# untitled.net
KiCad netlist of a schematic drawn in EAGLE
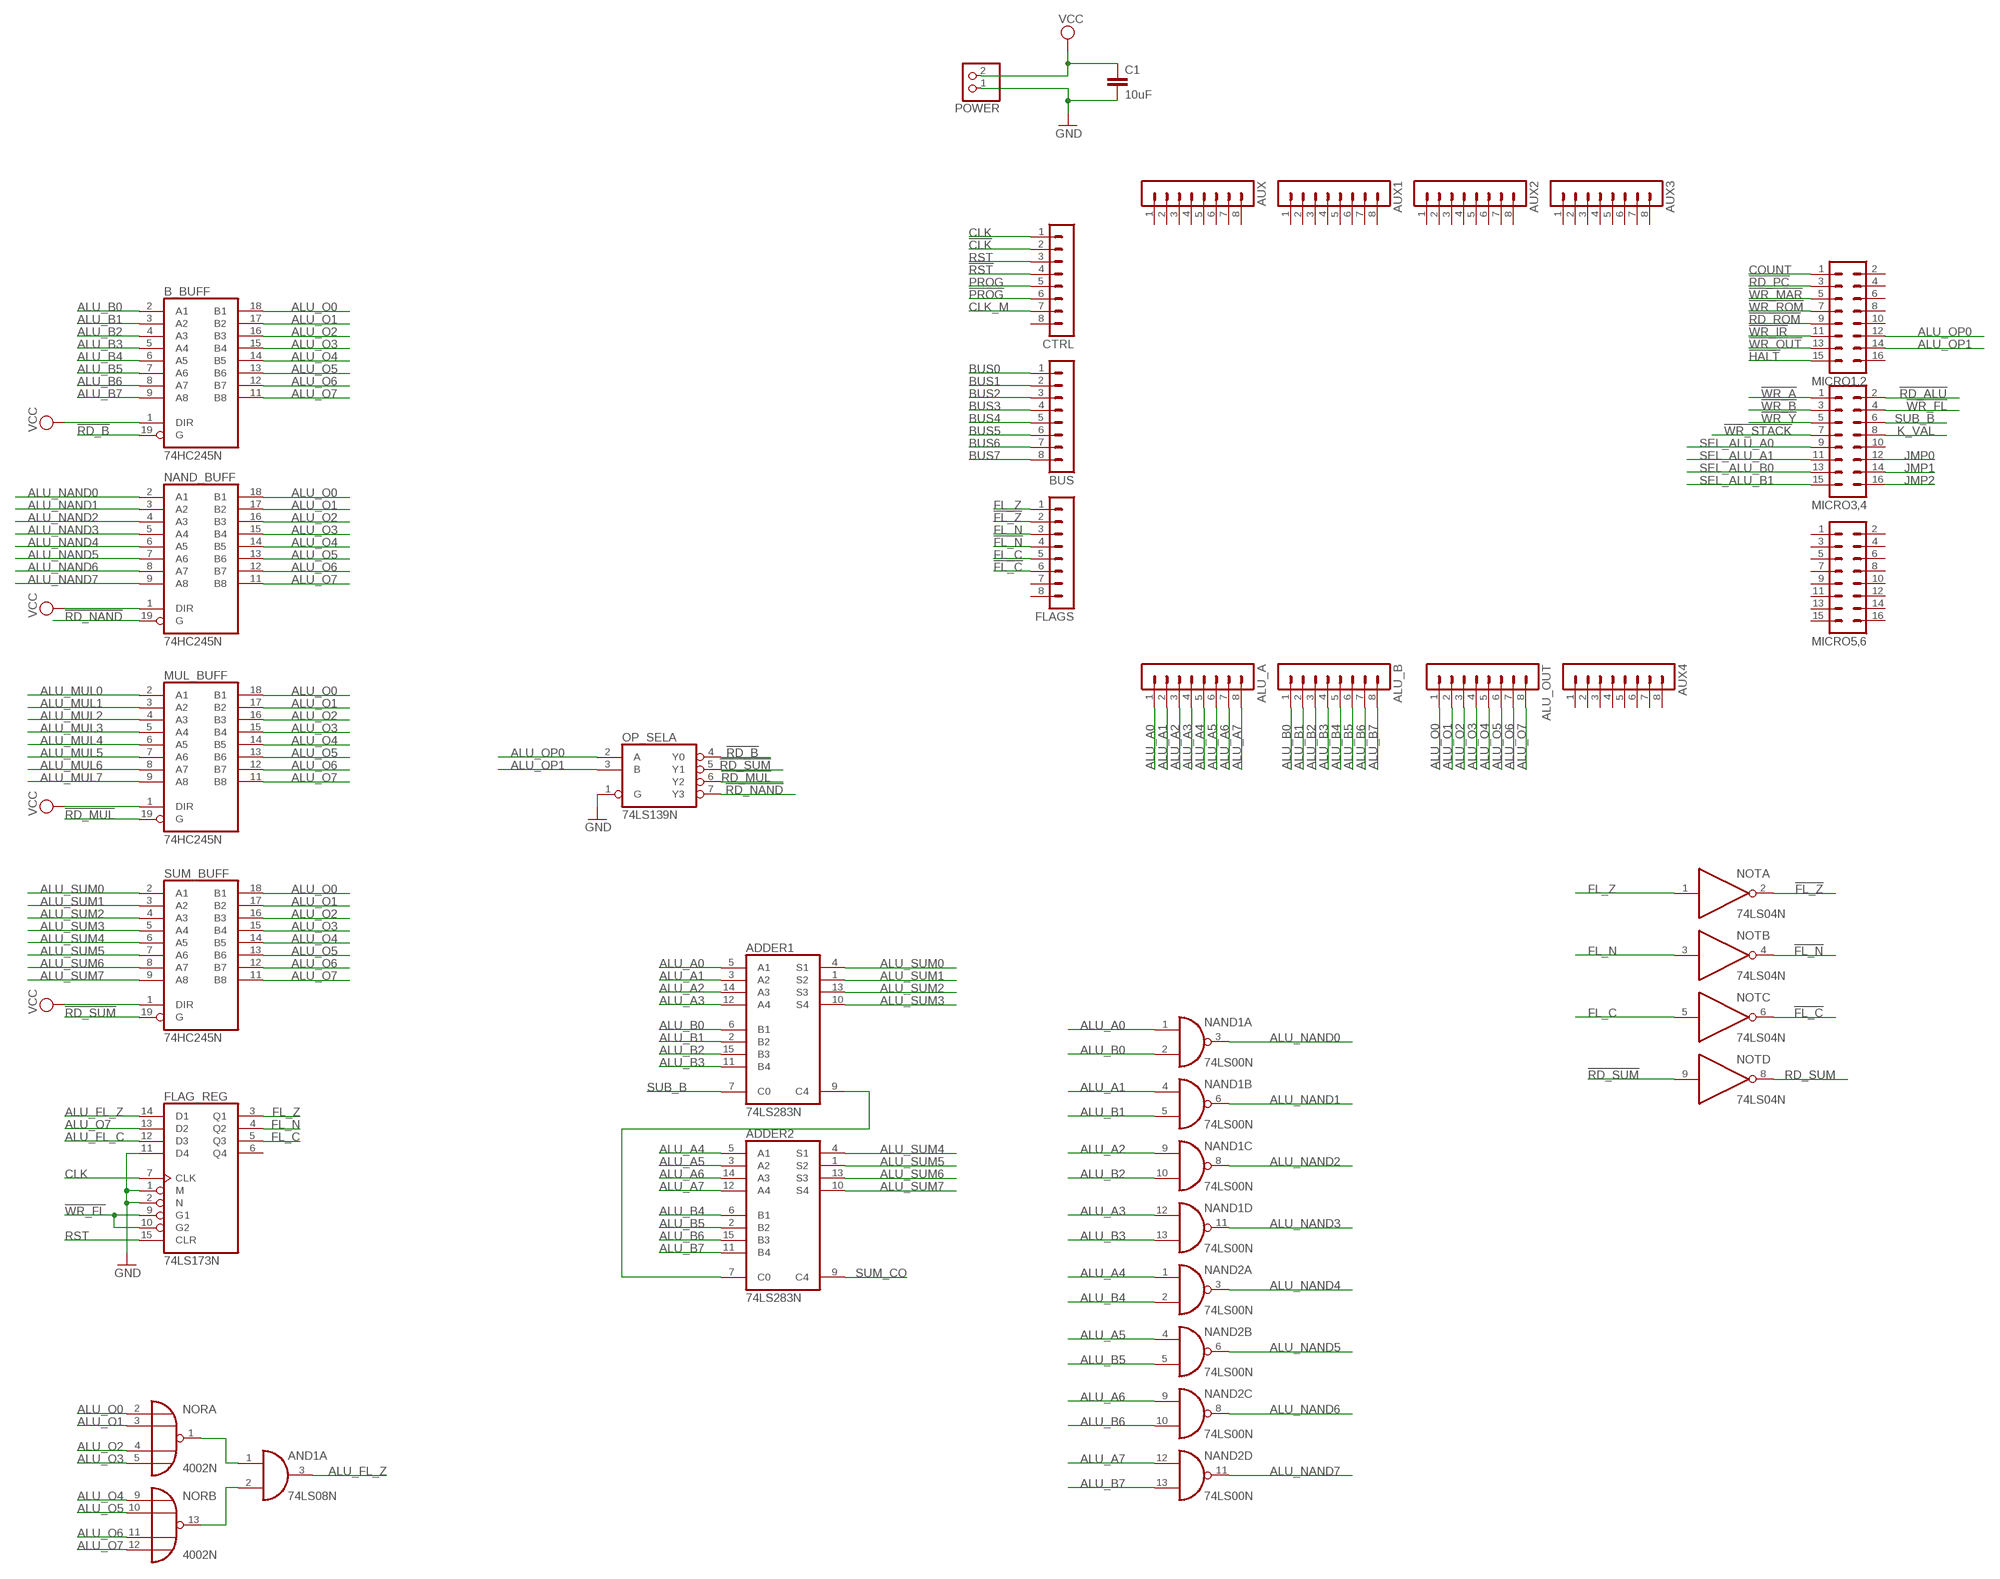
[diagram p0: schematic, sheet 1, part 1 of 2]
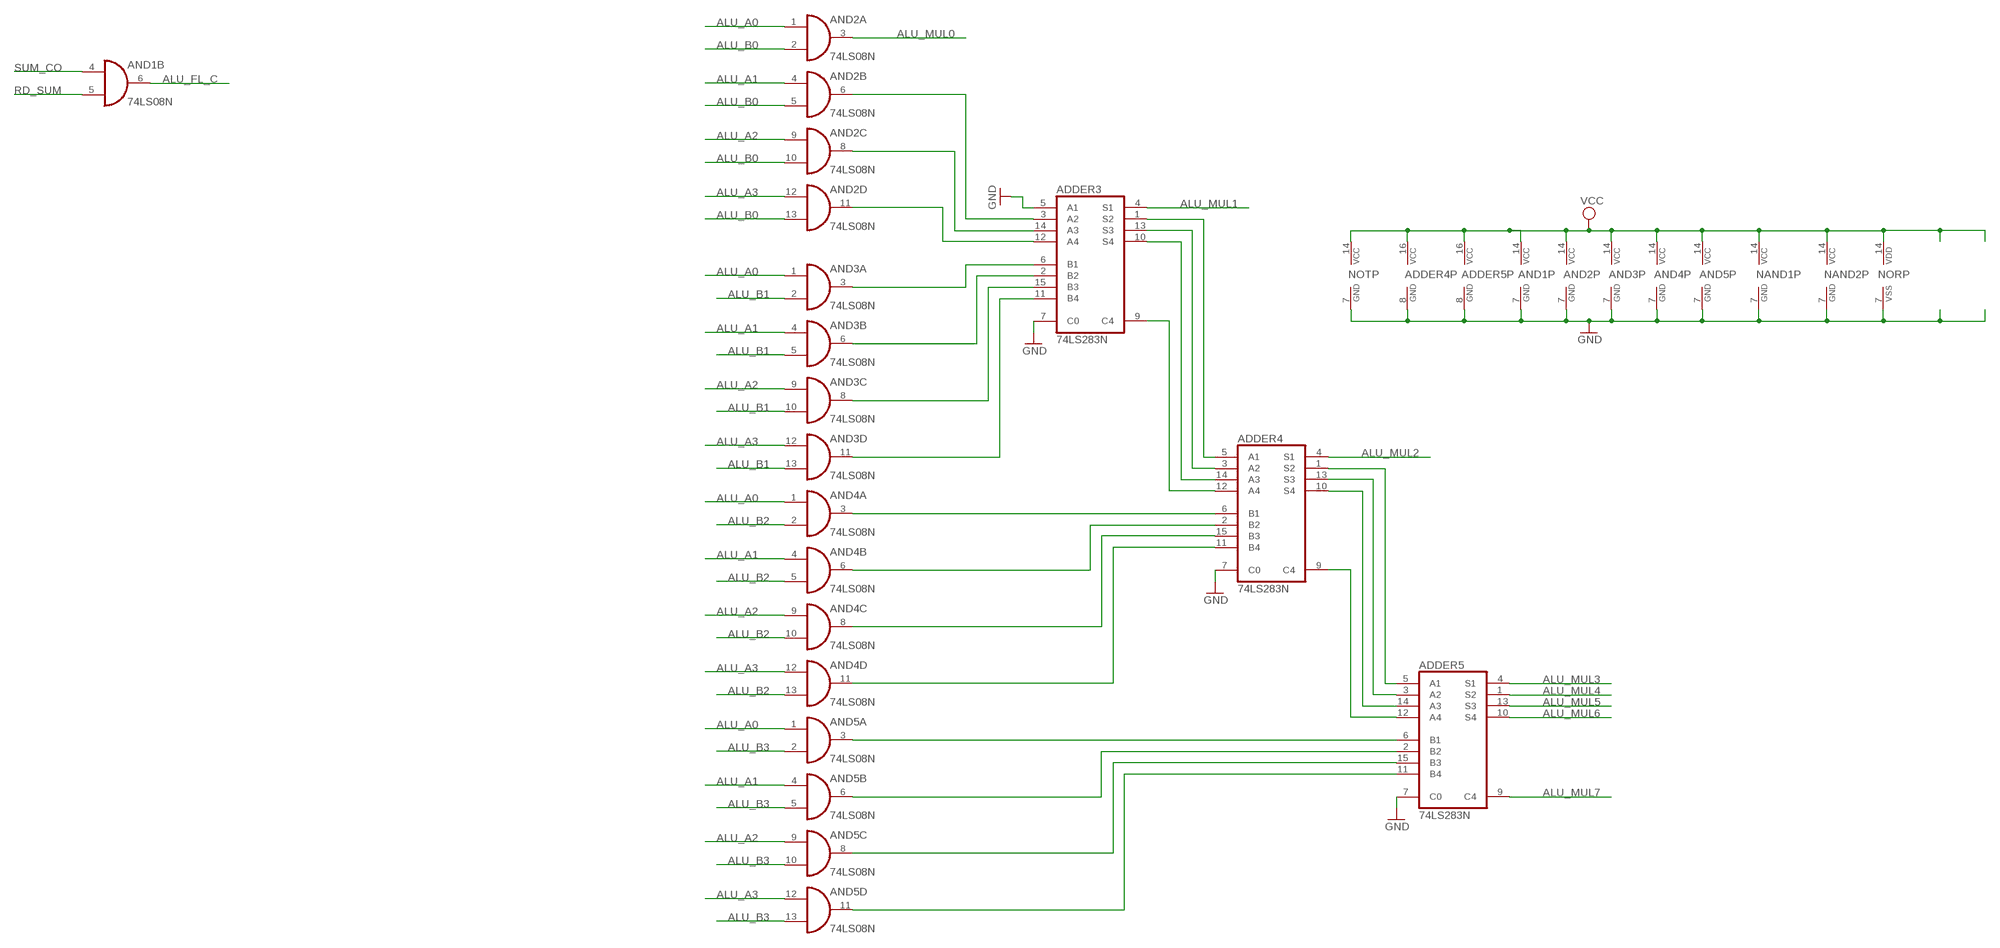
[diagram p1: schematic, sheet 1, part 2 of 2]

(export (version "E")
  (design (tool "Eeschema 10.0.6"))
  (components
    (comp (ref "ADDER1")
      (value "74LS283N")
      (footprint "eagle-import:DIL16")
      (libsource (lib "eagle-import") (part "74283NLS"))
    )
    (comp (ref "ADDER2")
      (value "74LS283N")
      (footprint "eagle-import:DIL16")
      (libsource (lib "eagle-import") (part "74283NLS"))
    )
    (comp (ref "ADDER3")
      (value "74LS283N")
      (footprint "eagle-import:DIL16")
      (libsource (lib "eagle-import") (part "74283NLS"))
    )
    (comp (ref "ADDER4")
      (value "74LS283N")
      (footprint "eagle-import:DIL16")
      (libsource (lib "eagle-import") (part "74283NLS"))
    )
    (comp (ref "ADDER5")
      (value "74LS283N")
      (footprint "eagle-import:DIL16")
      (libsource (lib "eagle-import") (part "74283NLS"))
    )
    (comp (ref "ALU_A")
      (value "MA08-1")
      (footprint "eagle-import:MA08-1")
      (libsource (lib "eagle-import") (part "MA08-1"))
    )
    (comp (ref "ALU_B")
      (value "MA08-1")
      (footprint "eagle-import:MA08-1")
      (libsource (lib "eagle-import") (part "MA08-1"))
    )
    (comp (ref "ALU_OUT")
      (value "MA08-1")
      (footprint "eagle-import:MA08-1")
      (libsource (lib "eagle-import") (part "MA08-1"))
    )
    (comp (ref "AND1")
      (value "74LS08N")
      (footprint "eagle-import:DIL14")
      (libsource (lib "eagle-import") (part "7408NLS"))
    )
    (comp (ref "AND2")
      (value "74LS08N")
      (footprint "eagle-import:DIL14")
      (libsource (lib "eagle-import") (part "7408NLS"))
    )
    (comp (ref "AND3")
      (value "74LS08N")
      (footprint "eagle-import:DIL14")
      (libsource (lib "eagle-import") (part "7408NLS"))
    )
    (comp (ref "AND4")
      (value "74LS08N")
      (footprint "eagle-import:DIL14")
      (libsource (lib "eagle-import") (part "7408NLS"))
    )
    (comp (ref "AND5")
      (value "74LS08N")
      (footprint "eagle-import:DIL14")
      (libsource (lib "eagle-import") (part "7408NLS"))
    )
    (comp (ref "AUX")
      (value "MA08-1")
      (footprint "eagle-import:MA08-1")
      (libsource (lib "eagle-import") (part "MA08-1"))
    )
    (comp (ref "AUX1")
      (value "MA08-1")
      (footprint "eagle-import:MA08-1")
      (libsource (lib "eagle-import") (part "MA08-1"))
    )
    (comp (ref "AUX2")
      (value "MA08-1")
      (footprint "eagle-import:MA08-1")
      (libsource (lib "eagle-import") (part "MA08-1"))
    )
    (comp (ref "AUX3")
      (value "MA08-1")
      (footprint "eagle-import:MA08-1")
      (libsource (lib "eagle-import") (part "MA08-1"))
    )
    (comp (ref "AUX4")
      (value "MA08-1")
      (footprint "eagle-import:MA08-1")
      (libsource (lib "eagle-import") (part "MA08-1"))
    )
    (comp (ref "BUS")
      (value "MA08-1")
      (footprint "eagle-import:MA08-1")
      (libsource (lib "eagle-import") (part "MA08-1"))
    )
    (comp (ref "B_BUFF")
      (value "74HC245N")
      (footprint "eagle-import:DIL20")
      (libsource (lib "eagle-import") (part "74245NHC"))
    )
    (comp (ref "C1")
      (value "10uF")
      (footprint "eagle-import:C025-050X050")
      (libsource (lib "eagle-import") (part "C-EU025-050X050"))
    )
    (comp (ref "CTRL")
      (value "MA08-1")
      (footprint "eagle-import:MA08-1")
      (libsource (lib "eagle-import") (part "MA08-1"))
    )
    (comp (ref "FLAGS")
      (value "MA08-1")
      (footprint "eagle-import:MA08-1")
      (libsource (lib "eagle-import") (part "MA08-1"))
    )
    (comp (ref "FLAG_REG")
      (value "74LS173N")
      (footprint "eagle-import:DIL16")
      (libsource (lib "eagle-import") (part "74173NLS"))
    )
    (comp (ref "MICRO1,2")
      (value "MA08-2")
      (footprint "eagle-import:MA08-2")
      (libsource (lib "eagle-import") (part "MA08-2"))
    )
    (comp (ref "MICRO3,4")
      (value "MA08-2")
      (footprint "eagle-import:MA08-2")
      (libsource (lib "eagle-import") (part "MA08-2"))
    )
    (comp (ref "MICRO5,6")
      (value "MA08-2")
      (footprint "eagle-import:MA08-2")
      (libsource (lib "eagle-import") (part "MA08-2"))
    )
    (comp (ref "MUL_BUFF")
      (value "74HC245N")
      (footprint "eagle-import:DIL20")
      (libsource (lib "eagle-import") (part "74245NHC"))
    )
    (comp (ref "NAND1")
      (value "74LS00N")
      (footprint "eagle-import:DIL14")
      (libsource (lib "eagle-import") (part "7400NLS"))
    )
    (comp (ref "NAND2")
      (value "74LS00N")
      (footprint "eagle-import:DIL14")
      (libsource (lib "eagle-import") (part "7400NLS"))
    )
    (comp (ref "NAND_BUFF")
      (value "74HC245N")
      (footprint "eagle-import:DIL20")
      (libsource (lib "eagle-import") (part "74245NHC"))
    )
    (comp (ref "NOR")
      (value "4002N")
      (footprint "eagle-import:DIL14")
      (libsource (lib "eagle-import") (part "4002N"))
    )
    (comp (ref "NOT")
      (value "74LS04N")
      (footprint "eagle-import:DIL14")
      (libsource (lib "eagle-import") (part "7404NLS"))
    )
    (comp (ref "OP_SEL")
      (value "74LS139N")
      (footprint "eagle-import:DIL16")
      (libsource (lib "eagle-import") (part "74139NLS"))
    )
    (comp (ref "POWER")
      (value "PINHD-1X2")
      (footprint "eagle-import:1X02")
      (libsource (lib "eagle-import") (part "PINHD-1X2"))
    )
    (comp (ref "SUM_BUFF")
      (value "74HC245N")
      (footprint "eagle-import:DIL20")
      (libsource (lib "eagle-import") (part "74245NHC"))
    )
  )
  (nets
    (net (code "1") (name "ALU_A0") (class "Default")
      (node (ref "ADDER1") (pin "5") (pinfunction "A1_5") (pintype "input"))
      (node (ref "ALU_A") (pin "1") (pinfunction "1_1") (pintype "passive"))
      (node (ref "AND2") (pin "1") (pinfunction "I0_1") (pintype "input"))
      (node (ref "AND3") (pin "1") (pinfunction "I0_1") (pintype "input"))
      (node (ref "AND4") (pin "1") (pinfunction "I0_1") (pintype "input"))
      (node (ref "AND5") (pin "1") (pinfunction "I0_1") (pintype "input"))
      (node (ref "NAND1") (pin "1") (pinfunction "I0_1") (pintype "input"))
    )
    (net (code "2") (name "ALU_A1") (class "Default")
      (node (ref "ADDER1") (pin "3") (pinfunction "A2_3") (pintype "input"))
      (node (ref "ALU_A") (pin "2") (pinfunction "2_2") (pintype "passive"))
      (node (ref "AND2") (pin "4") (pinfunction "I0_4") (pintype "input"))
      (node (ref "AND3") (pin "4") (pinfunction "I0_4") (pintype "input"))
      (node (ref "AND4") (pin "4") (pinfunction "I0_4") (pintype "input"))
      (node (ref "AND5") (pin "4") (pinfunction "I0_4") (pintype "input"))
      (node (ref "NAND1") (pin "4") (pinfunction "I0_4") (pintype "input"))
    )
    (net (code "3") (name "ALU_A2") (class "Default")
      (node (ref "ADDER1") (pin "14") (pinfunction "A3_14") (pintype "input"))
      (node (ref "ALU_A") (pin "3") (pinfunction "3_3") (pintype "passive"))
      (node (ref "AND2") (pin "9") (pinfunction "I0_9") (pintype "input"))
      (node (ref "AND3") (pin "9") (pinfunction "I0_9") (pintype "input"))
      (node (ref "AND4") (pin "9") (pinfunction "I0_9") (pintype "input"))
      (node (ref "AND5") (pin "9") (pinfunction "I0_9") (pintype "input"))
      (node (ref "NAND1") (pin "9") (pinfunction "I0_9") (pintype "input"))
    )
    (net (code "4") (name "ALU_A3") (class "Default")
      (node (ref "ADDER1") (pin "12") (pinfunction "A4_12") (pintype "input"))
      (node (ref "ALU_A") (pin "4") (pinfunction "4_4") (pintype "passive"))
      (node (ref "AND2") (pin "12") (pinfunction "I0_12") (pintype "input"))
      (node (ref "AND3") (pin "12") (pinfunction "I0_12") (pintype "input"))
      (node (ref "AND4") (pin "12") (pinfunction "I0_12") (pintype "input"))
      (node (ref "AND5") (pin "12") (pinfunction "I0_12") (pintype "input"))
      (node (ref "NAND1") (pin "12") (pinfunction "I0_12") (pintype "input"))
    )
    (net (code "5") (name "ALU_A4") (class "Default")
      (node (ref "ADDER2") (pin "5") (pinfunction "A1_5") (pintype "input"))
      (node (ref "ALU_A") (pin "5") (pinfunction "5_5") (pintype "passive"))
      (node (ref "NAND2") (pin "1") (pinfunction "I0_1") (pintype "input"))
    )
    (net (code "6") (name "ALU_A5") (class "Default")
      (node (ref "ADDER2") (pin "3") (pinfunction "A2_3") (pintype "input"))
      (node (ref "ALU_A") (pin "6") (pinfunction "6_6") (pintype "passive"))
      (node (ref "NAND2") (pin "4") (pinfunction "I0_4") (pintype "input"))
    )
    (net (code "7") (name "ALU_A6") (class "Default")
      (node (ref "ADDER2") (pin "14") (pinfunction "A3_14") (pintype "input"))
      (node (ref "ALU_A") (pin "7") (pinfunction "7_7") (pintype "passive"))
      (node (ref "NAND2") (pin "9") (pinfunction "I0_9") (pintype "input"))
    )
    (net (code "8") (name "ALU_A7") (class "Default")
      (node (ref "ADDER2") (pin "12") (pinfunction "A4_12") (pintype "input"))
      (node (ref "ALU_A") (pin "8") (pinfunction "8_8") (pintype "passive"))
      (node (ref "NAND2") (pin "12") (pinfunction "I0_12") (pintype "input"))
    )
    (net (code "9") (name "ALU_B0") (class "Default")
      (node (ref "ADDER1") (pin "6") (pinfunction "B1_6") (pintype "input"))
      (node (ref "ALU_B") (pin "1") (pinfunction "1_1") (pintype "passive"))
      (node (ref "AND2") (pin "10") (pinfunction "I1_10") (pintype "input"))
      (node (ref "AND2") (pin "13") (pinfunction "I1_13") (pintype "input"))
      (node (ref "AND2") (pin "2") (pinfunction "I1_2") (pintype "input"))
      (node (ref "AND2") (pin "5") (pinfunction "I1_5") (pintype "input"))
      (node (ref "B_BUFF") (pin "2") (pinfunction "A1_2") (pintype "bidirectional"))
      (node (ref "NAND1") (pin "2") (pinfunction "I1_2") (pintype "input"))
    )
    (net (code "10") (name "ALU_B1") (class "Default")
      (node (ref "ADDER1") (pin "2") (pinfunction "B2_2") (pintype "input"))
      (node (ref "ALU_B") (pin "2") (pinfunction "2_2") (pintype "passive"))
      (node (ref "AND3") (pin "10") (pinfunction "I1_10") (pintype "input"))
      (node (ref "AND3") (pin "13") (pinfunction "I1_13") (pintype "input"))
      (node (ref "AND3") (pin "2") (pinfunction "I1_2") (pintype "input"))
      (node (ref "AND3") (pin "5") (pinfunction "I1_5") (pintype "input"))
      (node (ref "B_BUFF") (pin "3") (pinfunction "A2_3") (pintype "bidirectional"))
      (node (ref "NAND1") (pin "5") (pinfunction "I1_5") (pintype "input"))
    )
    (net (code "11") (name "ALU_B2") (class "Default")
      (node (ref "ADDER1") (pin "15") (pinfunction "B3_15") (pintype "input"))
      (node (ref "ALU_B") (pin "3") (pinfunction "3_3") (pintype "passive"))
      (node (ref "AND4") (pin "10") (pinfunction "I1_10") (pintype "input"))
      (node (ref "AND4") (pin "13") (pinfunction "I1_13") (pintype "input"))
      (node (ref "AND4") (pin "2") (pinfunction "I1_2") (pintype "input"))
      (node (ref "AND4") (pin "5") (pinfunction "I1_5") (pintype "input"))
      (node (ref "B_BUFF") (pin "4") (pinfunction "A3_4") (pintype "bidirectional"))
      (node (ref "NAND1") (pin "10") (pinfunction "I1_10") (pintype "input"))
    )
    (net (code "12") (name "ALU_B3") (class "Default")
      (node (ref "ADDER1") (pin "11") (pinfunction "B4_11") (pintype "input"))
      (node (ref "ALU_B") (pin "4") (pinfunction "4_4") (pintype "passive"))
      (node (ref "AND5") (pin "10") (pinfunction "I1_10") (pintype "input"))
      (node (ref "AND5") (pin "13") (pinfunction "I1_13") (pintype "input"))
      (node (ref "AND5") (pin "2") (pinfunction "I1_2") (pintype "input"))
      (node (ref "AND5") (pin "5") (pinfunction "I1_5") (pintype "input"))
      (node (ref "B_BUFF") (pin "5") (pinfunction "A4_5") (pintype "bidirectional"))
      (node (ref "NAND1") (pin "13") (pinfunction "I1_13") (pintype "input"))
    )
    (net (code "13") (name "ALU_B4") (class "Default")
      (node (ref "ADDER2") (pin "6") (pinfunction "B1_6") (pintype "input"))
      (node (ref "ALU_B") (pin "5") (pinfunction "5_5") (pintype "passive"))
      (node (ref "B_BUFF") (pin "6") (pinfunction "A5_6") (pintype "bidirectional"))
      (node (ref "NAND2") (pin "2") (pinfunction "I1_2") (pintype "input"))
    )
    (net (code "14") (name "ALU_B5") (class "Default")
      (node (ref "ADDER2") (pin "2") (pinfunction "B2_2") (pintype "input"))
      (node (ref "ALU_B") (pin "6") (pinfunction "6_6") (pintype "passive"))
      (node (ref "B_BUFF") (pin "7") (pinfunction "A6_7") (pintype "bidirectional"))
      (node (ref "NAND2") (pin "5") (pinfunction "I1_5") (pintype "input"))
    )
    (net (code "15") (name "ALU_B6") (class "Default")
      (node (ref "ADDER2") (pin "15") (pinfunction "B3_15") (pintype "input"))
      (node (ref "ALU_B") (pin "7") (pinfunction "7_7") (pintype "passive"))
      (node (ref "B_BUFF") (pin "8") (pinfunction "A7_8") (pintype "bidirectional"))
      (node (ref "NAND2") (pin "10") (pinfunction "I1_10") (pintype "input"))
    )
    (net (code "16") (name "ALU_B7") (class "Default")
      (node (ref "ADDER2") (pin "11") (pinfunction "B4_11") (pintype "input"))
      (node (ref "ALU_B") (pin "8") (pinfunction "8_8") (pintype "passive"))
      (node (ref "B_BUFF") (pin "9") (pinfunction "A8_9") (pintype "bidirectional"))
      (node (ref "NAND2") (pin "13") (pinfunction "I1_13") (pintype "input"))
    )
    (net (code "17") (name "ALU_FL_C") (class "Default")
      (node (ref "AND1") (pin "6") (pinfunction "O_6") (pintype "output"))
      (node (ref "FLAG_REG") (pin "12") (pinfunction "D3_12") (pintype "input"))
    )
    (net (code "18") (name "ALU_FL_Z") (class "Default")
      (node (ref "AND1") (pin "3") (pinfunction "O_3") (pintype "output"))
      (node (ref "FLAG_REG") (pin "14") (pinfunction "D1_14") (pintype "input"))
    )
    (net (code "19") (name "ALU_MUL0") (class "Default")
      (node (ref "AND2") (pin "3") (pinfunction "O_3") (pintype "output"))
      (node (ref "MUL_BUFF") (pin "2") (pinfunction "A1_2") (pintype "bidirectional"))
    )
    (net (code "20") (name "ALU_MUL1") (class "Default")
      (node (ref "ADDER3") (pin "4") (pinfunction "S1_4") (pintype "output"))
      (node (ref "MUL_BUFF") (pin "3") (pinfunction "A2_3") (pintype "bidirectional"))
    )
    (net (code "21") (name "ALU_MUL2") (class "Default")
      (node (ref "ADDER4") (pin "4") (pinfunction "S1_4") (pintype "output"))
      (node (ref "MUL_BUFF") (pin "4") (pinfunction "A3_4") (pintype "bidirectional"))
    )
    (net (code "22") (name "ALU_MUL3") (class "Default")
      (node (ref "ADDER5") (pin "4") (pinfunction "S1_4") (pintype "output"))
      (node (ref "MUL_BUFF") (pin "5") (pinfunction "A4_5") (pintype "bidirectional"))
    )
    (net (code "23") (name "ALU_MUL4") (class "Default")
      (node (ref "ADDER5") (pin "1") (pinfunction "S2_1") (pintype "output"))
      (node (ref "MUL_BUFF") (pin "6") (pinfunction "A5_6") (pintype "bidirectional"))
    )
    (net (code "24") (name "ALU_MUL5") (class "Default")
      (node (ref "ADDER5") (pin "13") (pinfunction "S3_13") (pintype "output"))
      (node (ref "MUL_BUFF") (pin "7") (pinfunction "A6_7") (pintype "bidirectional"))
    )
    (net (code "25") (name "ALU_MUL6") (class "Default")
      (node (ref "ADDER5") (pin "10") (pinfunction "S4_10") (pintype "output"))
      (node (ref "MUL_BUFF") (pin "8") (pinfunction "A7_8") (pintype "bidirectional"))
    )
    (net (code "26") (name "ALU_MUL7") (class "Default")
      (node (ref "ADDER5") (pin "9") (pinfunction "C4_9") (pintype "output"))
      (node (ref "MUL_BUFF") (pin "9") (pinfunction "A8_9") (pintype "bidirectional"))
    )
    (net (code "27") (name "ALU_NAND0") (class "Default")
      (node (ref "NAND1") (pin "3") (pinfunction "O_3") (pintype "output"))
      (node (ref "NAND_BUFF") (pin "2") (pinfunction "A1_2") (pintype "bidirectional"))
    )
    (net (code "28") (name "ALU_NAND1") (class "Default")
      (node (ref "NAND1") (pin "6") (pinfunction "O_6") (pintype "output"))
      (node (ref "NAND_BUFF") (pin "3") (pinfunction "A2_3") (pintype "bidirectional"))
    )
    (net (code "29") (name "ALU_NAND2") (class "Default")
      (node (ref "NAND1") (pin "8") (pinfunction "O_8") (pintype "output"))
      (node (ref "NAND_BUFF") (pin "4") (pinfunction "A3_4") (pintype "bidirectional"))
    )
    (net (code "30") (name "ALU_NAND3") (class "Default")
      (node (ref "NAND1") (pin "11") (pinfunction "O_11") (pintype "output"))
      (node (ref "NAND_BUFF") (pin "5") (pinfunction "A4_5") (pintype "bidirectional"))
    )
    (net (code "31") (name "ALU_NAND4") (class "Default")
      (node (ref "NAND2") (pin "3") (pinfunction "O_3") (pintype "output"))
      (node (ref "NAND_BUFF") (pin "6") (pinfunction "A5_6") (pintype "bidirectional"))
    )
    (net (code "32") (name "ALU_NAND5") (class "Default")
      (node (ref "NAND2") (pin "6") (pinfunction "O_6") (pintype "output"))
      (node (ref "NAND_BUFF") (pin "7") (pinfunction "A6_7") (pintype "bidirectional"))
    )
    (net (code "33") (name "ALU_NAND6") (class "Default")
      (node (ref "NAND2") (pin "8") (pinfunction "O_8") (pintype "output"))
      (node (ref "NAND_BUFF") (pin "8") (pinfunction "A7_8") (pintype "bidirectional"))
    )
    (net (code "34") (name "ALU_NAND7") (class "Default")
      (node (ref "NAND2") (pin "11") (pinfunction "O_11") (pintype "output"))
      (node (ref "NAND_BUFF") (pin "9") (pinfunction "A8_9") (pintype "bidirectional"))
    )
    (net (code "35") (name "ALU_O0") (class "Default")
      (node (ref "ALU_OUT") (pin "1") (pinfunction "1_1") (pintype "passive"))
      (node (ref "B_BUFF") (pin "18") (pinfunction "B1_18") (pintype "bidirectional"))
      (node (ref "MUL_BUFF") (pin "18") (pinfunction "B1_18") (pintype "bidirectional"))
      (node (ref "NAND_BUFF") (pin "18") (pinfunction "B1_18") (pintype "bidirectional"))
      (node (ref "NOR") (pin "2") (pinfunction "I0_2") (pintype "input"))
      (node (ref "SUM_BUFF") (pin "18") (pinfunction "B1_18") (pintype "bidirectional"))
    )
    (net (code "36") (name "ALU_O1") (class "Default")
      (node (ref "ALU_OUT") (pin "2") (pinfunction "2_2") (pintype "passive"))
      (node (ref "B_BUFF") (pin "17") (pinfunction "B2_17") (pintype "bidirectional"))
      (node (ref "MUL_BUFF") (pin "17") (pinfunction "B2_17") (pintype "bidirectional"))
      (node (ref "NAND_BUFF") (pin "17") (pinfunction "B2_17") (pintype "bidirectional"))
      (node (ref "NOR") (pin "3") (pinfunction "I1_3") (pintype "input"))
      (node (ref "SUM_BUFF") (pin "17") (pinfunction "B2_17") (pintype "bidirectional"))
    )
    (net (code "37") (name "ALU_O2") (class "Default")
      (node (ref "ALU_OUT") (pin "3") (pinfunction "3_3") (pintype "passive"))
      (node (ref "B_BUFF") (pin "16") (pinfunction "B3_16") (pintype "bidirectional"))
      (node (ref "MUL_BUFF") (pin "16") (pinfunction "B3_16") (pintype "bidirectional"))
      (node (ref "NAND_BUFF") (pin "16") (pinfunction "B3_16") (pintype "bidirectional"))
      (node (ref "NOR") (pin "4") (pinfunction "I2_4") (pintype "input"))
      (node (ref "SUM_BUFF") (pin "16") (pinfunction "B3_16") (pintype "bidirectional"))
    )
    (net (code "38") (name "ALU_O3") (class "Default")
      (node (ref "ALU_OUT") (pin "4") (pinfunction "4_4") (pintype "passive"))
      (node (ref "B_BUFF") (pin "15") (pinfunction "B4_15") (pintype "bidirectional"))
      (node (ref "MUL_BUFF") (pin "15") (pinfunction "B4_15") (pintype "bidirectional"))
      (node (ref "NAND_BUFF") (pin "15") (pinfunction "B4_15") (pintype "bidirectional"))
      (node (ref "NOR") (pin "5") (pinfunction "I3_5") (pintype "input"))
      (node (ref "SUM_BUFF") (pin "15") (pinfunction "B4_15") (pintype "bidirectional"))
    )
    (net (code "39") (name "ALU_O4") (class "Default")
      (node (ref "ALU_OUT") (pin "5") (pinfunction "5_5") (pintype "passive"))
      (node (ref "B_BUFF") (pin "14") (pinfunction "B5_14") (pintype "bidirectional"))
      (node (ref "MUL_BUFF") (pin "14") (pinfunction "B5_14") (pintype "bidirectional"))
      (node (ref "NAND_BUFF") (pin "14") (pinfunction "B5_14") (pintype "bidirectional"))
      (node (ref "NOR") (pin "9") (pinfunction "I0_9") (pintype "input"))
      (node (ref "SUM_BUFF") (pin "14") (pinfunction "B5_14") (pintype "bidirectional"))
    )
    (net (code "40") (name "ALU_O5") (class "Default")
      (node (ref "ALU_OUT") (pin "6") (pinfunction "6_6") (pintype "passive"))
      (node (ref "B_BUFF") (pin "13") (pinfunction "B6_13") (pintype "bidirectional"))
      (node (ref "MUL_BUFF") (pin "13") (pinfunction "B6_13") (pintype "bidirectional"))
      (node (ref "NAND_BUFF") (pin "13") (pinfunction "B6_13") (pintype "bidirectional"))
      (node (ref "NOR") (pin "10") (pinfunction "I1_10") (pintype "input"))
      (node (ref "SUM_BUFF") (pin "13") (pinfunction "B6_13") (pintype "bidirectional"))
    )
    (net (code "41") (name "ALU_O6") (class "Default")
      (node (ref "ALU_OUT") (pin "7") (pinfunction "7_7") (pintype "passive"))
      (node (ref "B_BUFF") (pin "12") (pinfunction "B7_12") (pintype "bidirectional"))
      (node (ref "MUL_BUFF") (pin "12") (pinfunction "B7_12") (pintype "bidirectional"))
      (node (ref "NAND_BUFF") (pin "12") (pinfunction "B7_12") (pintype "bidirectional"))
      (node (ref "NOR") (pin "11") (pinfunction "I2_11") (pintype "input"))
      (node (ref "SUM_BUFF") (pin "12") (pinfunction "B7_12") (pintype "bidirectional"))
    )
    (net (code "42") (name "ALU_O7") (class "Default")
      (node (ref "ALU_OUT") (pin "8") (pinfunction "8_8") (pintype "passive"))
      (node (ref "B_BUFF") (pin "11") (pinfunction "B8_11") (pintype "bidirectional"))
      (node (ref "FLAG_REG") (pin "13") (pinfunction "D2_13") (pintype "input"))
      (node (ref "MUL_BUFF") (pin "11") (pinfunction "B8_11") (pintype "bidirectional"))
      (node (ref "NAND_BUFF") (pin "11") (pinfunction "B8_11") (pintype "bidirectional"))
      (node (ref "NOR") (pin "12") (pinfunction "I3_12") (pintype "input"))
      (node (ref "SUM_BUFF") (pin "11") (pinfunction "B8_11") (pintype "bidirectional"))
    )
    (net (code "43") (name "ALU_OP0") (class "Default")
      (node (ref "MICRO1,2") (pin "12") (pinfunction "12_12") (pintype "passive"))
      (node (ref "OP_SEL") (pin "2") (pinfunction "A_2") (pintype "input"))
    )
    (net (code "44") (name "ALU_OP1") (class "Default")
      (node (ref "MICRO1,2") (pin "14") (pinfunction "14_14") (pintype "passive"))
      (node (ref "OP_SEL") (pin "3") (pinfunction "B_3") (pintype "input"))
    )
    (net (code "45") (name "ALU_SUM0") (class "Default")
      (node (ref "ADDER1") (pin "4") (pinfunction "S1_4") (pintype "output"))
      (node (ref "SUM_BUFF") (pin "2") (pinfunction "A1_2") (pintype "bidirectional"))
    )
    (net (code "46") (name "ALU_SUM1") (class "Default")
      (node (ref "ADDER1") (pin "1") (pinfunction "S2_1") (pintype "output"))
      (node (ref "SUM_BUFF") (pin "3") (pinfunction "A2_3") (pintype "bidirectional"))
    )
    (net (code "47") (name "ALU_SUM2") (class "Default")
      (node (ref "ADDER1") (pin "13") (pinfunction "S3_13") (pintype "output"))
      (node (ref "SUM_BUFF") (pin "4") (pinfunction "A3_4") (pintype "bidirectional"))
    )
    (net (code "48") (name "ALU_SUM3") (class "Default")
      (node (ref "ADDER1") (pin "10") (pinfunction "S4_10") (pintype "output"))
      (node (ref "SUM_BUFF") (pin "5") (pinfunction "A4_5") (pintype "bidirectional"))
    )
    (net (code "49") (name "ALU_SUM4") (class "Default")
      (node (ref "ADDER2") (pin "4") (pinfunction "S1_4") (pintype "output"))
      (node (ref "SUM_BUFF") (pin "6") (pinfunction "A5_6") (pintype "bidirectional"))
    )
    (net (code "50") (name "ALU_SUM5") (class "Default")
      (node (ref "ADDER2") (pin "1") (pinfunction "S2_1") (pintype "output"))
      (node (ref "SUM_BUFF") (pin "7") (pinfunction "A6_7") (pintype "bidirectional"))
    )
    (net (code "51") (name "ALU_SUM6") (class "Default")
      (node (ref "ADDER2") (pin "13") (pinfunction "S3_13") (pintype "output"))
      (node (ref "SUM_BUFF") (pin "8") (pinfunction "A7_8") (pintype "bidirectional"))
    )
    (net (code "52") (name "ALU_SUM7") (class "Default")
      (node (ref "ADDER2") (pin "10") (pinfunction "S4_10") (pintype "output"))
      (node (ref "SUM_BUFF") (pin "9") (pinfunction "A8_9") (pintype "bidirectional"))
    )
    (net (code "53") (name "BUS0") (class "Default")
      (node (ref "BUS") (pin "1") (pinfunction "1_1") (pintype "passive"))
    )
    (net (code "54") (name "BUS1") (class "Default")
      (node (ref "BUS") (pin "2") (pinfunction "2_2") (pintype "passive"))
    )
    (net (code "55") (name "BUS2") (class "Default")
      (node (ref "BUS") (pin "3") (pinfunction "3_3") (pintype "passive"))
    )
    (net (code "56") (name "BUS3") (class "Default")
      (node (ref "BUS") (pin "4") (pinfunction "4_4") (pintype "passive"))
    )
    (net (code "57") (name "BUS4") (class "Default")
      (node (ref "BUS") (pin "5") (pinfunction "5_5") (pintype "passive"))
    )
    (net (code "58") (name "BUS5") (class "Default")
      (node (ref "BUS") (pin "6") (pinfunction "6_6") (pintype "passive"))
    )
    (net (code "59") (name "BUS6") (class "Default")
      (node (ref "BUS") (pin "7") (pinfunction "7_7") (pintype "passive"))
    )
    (net (code "60") (name "BUS7") (class "Default")
      (node (ref "BUS") (pin "8") (pinfunction "8_8") (pintype "passive"))
    )
    (net (code "61") (name "CLK") (class "Default")
      (node (ref "CTRL") (pin "1") (pinfunction "1_1") (pintype "passive"))
      (node (ref "FLAG_REG") (pin "7") (pinfunction "CLK_7") (pintype "input"))
    )
    (net (code "62") (name "CLK_M") (class "Default")
      (node (ref "CTRL") (pin "7") (pinfunction "7_7") (pintype "passive"))
    )
    (net (code "63") (name "COUNT") (class "Default")
      (node (ref "MICRO1,2") (pin "1") (pinfunction "1_1") (pintype "passive"))
    )
    (net (code "64") (name "FL_C") (class "Default")
      (node (ref "FLAGS") (pin "5") (pinfunction "5_5") (pintype "passive"))
      (node (ref "FLAG_REG") (pin "5") (pinfunction "Q3_5") (pintype "tri_state"))
      (node (ref "NOT") (pin "5") (pinfunction "I_5") (pintype "input"))
    )
    (net (code "65") (name "FL_N") (class "Default")
      (node (ref "FLAGS") (pin "3") (pinfunction "3_3") (pintype "passive"))
      (node (ref "FLAG_REG") (pin "4") (pinfunction "Q2_4") (pintype "tri_state"))
      (node (ref "NOT") (pin "3") (pinfunction "I_3") (pintype "input"))
    )
    (net (code "66") (name "FL_Z") (class "Default")
      (node (ref "FLAGS") (pin "1") (pinfunction "1_1") (pintype "passive"))
      (node (ref "FLAG_REG") (pin "3") (pinfunction "Q1_3") (pintype "tri_state"))
      (node (ref "NOT") (pin "1") (pinfunction "I_1") (pintype "input"))
    )
    (net (code "67") (name "GND") (class "Default")
      (node (ref "ADDER3") (pin "5") (pinfunction "A1_5") (pintype "input"))
      (node (ref "ADDER3") (pin "7") (pinfunction "C0_7") (pintype "input"))
      (node (ref "ADDER4") (pin "7") (pinfunction "C0_7") (pintype "input"))
      (node (ref "ADDER4") (pin "8") (pinfunction "GND_8") (pintype "power_in"))
      (node (ref "ADDER5") (pin "7") (pinfunction "C0_7") (pintype "input"))
      (node (ref "ADDER5") (pin "8") (pinfunction "GND_8") (pintype "power_in"))
      (node (ref "AND1") (pin "7") (pinfunction "GND_7") (pintype "power_in"))
      (node (ref "AND2") (pin "7") (pinfunction "GND_7") (pintype "power_in"))
      (node (ref "AND3") (pin "7") (pinfunction "GND_7") (pintype "power_in"))
      (node (ref "AND4") (pin "7") (pinfunction "GND_7") (pintype "power_in"))
      (node (ref "AND5") (pin "7") (pinfunction "GND_7") (pintype "power_in"))
      (node (ref "C1") (pin "2") (pinfunction "2_2") (pintype "passive"))
      (node (ref "FLAG_REG") (pin "1") (pinfunction "M_1") (pintype "input"))
      (node (ref "FLAG_REG") (pin "11") (pinfunction "D4_11") (pintype "input"))
      (node (ref "FLAG_REG") (pin "2") (pinfunction "N_2") (pintype "input"))
      (node (ref "NAND1") (pin "7") (pinfunction "GND_7") (pintype "power_in"))
      (node (ref "NAND2") (pin "7") (pinfunction "GND_7") (pintype "power_in"))
      (node (ref "NOR") (pin "7") (pinfunction "VSS_7") (pintype "power_in"))
      (node (ref "NOT") (pin "7") (pinfunction "GND_7") (pintype "power_in"))
      (node (ref "OP_SEL") (pin "1") (pinfunction "G_1") (pintype "input"))
      (node (ref "POWER") (pin "1") (pinfunction "1_1") (pintype "passive"))
    )
    (net (code "68") (name "JMP0") (class "Default")
      (node (ref "MICRO3,4") (pin "12") (pinfunction "12_12") (pintype "passive"))
    )
    (net (code "69") (name "JMP1") (class "Default")
      (node (ref "MICRO3,4") (pin "14") (pinfunction "14_14") (pintype "passive"))
    )
    (net (code "70") (name "JMP2") (class "Default")
      (node (ref "MICRO3,4") (pin "16") (pinfunction "16_16") (pintype "passive"))
    )
    (net (code "71") (name "K_VAL") (class "Default")
      (node (ref "MICRO3,4") (pin "8") (pinfunction "8_8") (pintype "passive"))
    )
    (net (code "72") (name "Net-(ADDER1A-C4)") (class "Default")
      (node (ref "ADDER1") (pin "9") (pinfunction "C4_9") (pintype "output"))
      (node (ref "ADDER2") (pin "7") (pinfunction "C0_7") (pintype "input"))
    )
    (net (code "73") (name "Net-(ADDER3A-A2)") (class "Default")
      (node (ref "ADDER3") (pin "3") (pinfunction "A2_3") (pintype "input"))
      (node (ref "AND2") (pin "6") (pinfunction "O_6") (pintype "output"))
    )
    (net (code "74") (name "Net-(ADDER3A-A3)") (class "Default")
      (node (ref "ADDER3") (pin "14") (pinfunction "A3_14") (pintype "input"))
      (node (ref "AND2") (pin "8") (pinfunction "O_8") (pintype "output"))
    )
    (net (code "75") (name "Net-(ADDER3A-A4)") (class "Default")
      (node (ref "ADDER3") (pin "12") (pinfunction "A4_12") (pintype "input"))
      (node (ref "AND2") (pin "11") (pinfunction "O_11") (pintype "output"))
    )
    (net (code "76") (name "Net-(ADDER3A-B1)") (class "Default")
      (node (ref "ADDER3") (pin "6") (pinfunction "B1_6") (pintype "input"))
      (node (ref "AND3") (pin "3") (pinfunction "O_3") (pintype "output"))
    )
    (net (code "77") (name "Net-(ADDER3A-B2)") (class "Default")
      (node (ref "ADDER3") (pin "2") (pinfunction "B2_2") (pintype "input"))
      (node (ref "AND3") (pin "6") (pinfunction "O_6") (pintype "output"))
    )
    (net (code "78") (name "Net-(ADDER3A-B3)") (class "Default")
      (node (ref "ADDER3") (pin "15") (pinfunction "B3_15") (pintype "input"))
      (node (ref "AND3") (pin "8") (pinfunction "O_8") (pintype "output"))
    )
    (net (code "79") (name "Net-(ADDER3A-B4)") (class "Default")
      (node (ref "ADDER3") (pin "11") (pinfunction "B4_11") (pintype "input"))
      (node (ref "AND3") (pin "11") (pinfunction "O_11") (pintype "output"))
    )
    (net (code "80") (name "Net-(ADDER3A-C4)") (class "Default")
      (node (ref "ADDER3") (pin "9") (pinfunction "C4_9") (pintype "output"))
      (node (ref "ADDER4") (pin "12") (pinfunction "A4_12") (pintype "input"))
    )
    (net (code "81") (name "Net-(ADDER3A-S2)") (class "Default")
      (node (ref "ADDER3") (pin "1") (pinfunction "S2_1") (pintype "output"))
      (node (ref "ADDER4") (pin "5") (pinfunction "A1_5") (pintype "input"))
    )
    (net (code "82") (name "Net-(ADDER3A-S3)") (class "Default")
      (node (ref "ADDER3") (pin "13") (pinfunction "S3_13") (pintype "output"))
      (node (ref "ADDER4") (pin "3") (pinfunction "A2_3") (pintype "input"))
    )
    (net (code "83") (name "Net-(ADDER3A-S4)") (class "Default")
      (node (ref "ADDER3") (pin "10") (pinfunction "S4_10") (pintype "output"))
      (node (ref "ADDER4") (pin "14") (pinfunction "A3_14") (pintype "input"))
    )
    (net (code "84") (name "Net-(ADDER4A-B1)") (class "Default")
      (node (ref "ADDER4") (pin "6") (pinfunction "B1_6") (pintype "input"))
      (node (ref "AND4") (pin "3") (pinfunction "O_3") (pintype "output"))
    )
    (net (code "85") (name "Net-(ADDER4A-B2)") (class "Default")
      (node (ref "ADDER4") (pin "2") (pinfunction "B2_2") (pintype "input"))
      (node (ref "AND4") (pin "6") (pinfunction "O_6") (pintype "output"))
    )
    (net (code "86") (name "Net-(ADDER4A-B3)") (class "Default")
      (node (ref "ADDER4") (pin "15") (pinfunction "B3_15") (pintype "input"))
      (node (ref "AND4") (pin "8") (pinfunction "O_8") (pintype "output"))
    )
    (net (code "87") (name "Net-(ADDER4A-B4)") (class "Default")
      (node (ref "ADDER4") (pin "11") (pinfunction "B4_11") (pintype "input"))
      (node (ref "AND4") (pin "11") (pinfunction "O_11") (pintype "output"))
    )
    (net (code "88") (name "Net-(ADDER4A-C4)") (class "Default")
      (node (ref "ADDER4") (pin "9") (pinfunction "C4_9") (pintype "output"))
      (node (ref "ADDER5") (pin "12") (pinfunction "A4_12") (pintype "input"))
    )
    (net (code "89") (name "Net-(ADDER4A-S2)") (class "Default")
      (node (ref "ADDER4") (pin "1") (pinfunction "S2_1") (pintype "output"))
      (node (ref "ADDER5") (pin "5") (pinfunction "A1_5") (pintype "input"))
    )
    (net (code "90") (name "Net-(ADDER4A-S3)") (class "Default")
      (node (ref "ADDER4") (pin "13") (pinfunction "S3_13") (pintype "output"))
      (node (ref "ADDER5") (pin "3") (pinfunction "A2_3") (pintype "input"))
    )
    (net (code "91") (name "Net-(ADDER4A-S4)") (class "Default")
      (node (ref "ADDER4") (pin "10") (pinfunction "S4_10") (pintype "output"))
      (node (ref "ADDER5") (pin "14") (pinfunction "A3_14") (pintype "input"))
    )
    (net (code "92") (name "Net-(ADDER5A-B1)") (class "Default")
      (node (ref "ADDER5") (pin "6") (pinfunction "B1_6") (pintype "input"))
      (node (ref "AND5") (pin "3") (pinfunction "O_3") (pintype "output"))
    )
    (net (code "93") (name "Net-(ADDER5A-B2)") (class "Default")
      (node (ref "ADDER5") (pin "2") (pinfunction "B2_2") (pintype "input"))
      (node (ref "AND5") (pin "6") (pinfunction "O_6") (pintype "output"))
    )
    (net (code "94") (name "Net-(ADDER5A-B3)") (class "Default")
      (node (ref "ADDER5") (pin "15") (pinfunction "B3_15") (pintype "input"))
      (node (ref "AND5") (pin "8") (pinfunction "O_8") (pintype "output"))
    )
    (net (code "95") (name "Net-(ADDER5A-B4)") (class "Default")
      (node (ref "ADDER5") (pin "11") (pinfunction "B4_11") (pintype "input"))
      (node (ref "AND5") (pin "11") (pinfunction "O_11") (pintype "output"))
    )
    (net (code "96") (name "Net-(AND1A-I0)") (class "Default")
      (node (ref "AND1") (pin "1") (pinfunction "I0_1") (pintype "input"))
      (node (ref "NOR") (pin "1") (pinfunction "O_1") (pintype "output"))
    )
    (net (code "97") (name "Net-(AND1A-I1)") (class "Default")
      (node (ref "AND1") (pin "2") (pinfunction "I1_2") (pintype "input"))
      (node (ref "NOR") (pin "13") (pinfunction "O_13") (pintype "output"))
    )
    (net (code "98") (name "PROG") (class "Default")
      (node (ref "CTRL") (pin "5") (pinfunction "5_5") (pintype "passive"))
    )
    (net (code "99") (name "RD_SUM") (class "Default")
      (node (ref "AND1") (pin "5") (pinfunction "I1_5") (pintype "input"))
      (node (ref "NOT") (pin "8") (pinfunction "O_8") (pintype "output"))
    )
    (net (code "100") (name "RST") (class "Default")
      (node (ref "CTRL") (pin "3") (pinfunction "3_3") (pintype "passive"))
      (node (ref "FLAG_REG") (pin "15") (pinfunction "CLR_15") (pintype "input"))
    )
    (net (code "101") (name "SEL_ALU_A0") (class "Default")
      (node (ref "MICRO3,4") (pin "9") (pinfunction "9_9") (pintype "passive"))
    )
    (net (code "102") (name "SEL_ALU_A1") (class "Default")
      (node (ref "MICRO3,4") (pin "11") (pinfunction "11_11") (pintype "passive"))
    )
    (net (code "103") (name "SEL_ALU_B0") (class "Default")
      (node (ref "MICRO3,4") (pin "13") (pinfunction "13_13") (pintype "passive"))
    )
    (net (code "104") (name "SEL_ALU_B1") (class "Default")
      (node (ref "MICRO3,4") (pin "15") (pinfunction "15_15") (pintype "passive"))
    )
    (net (code "105") (name "SUB_B") (class "Default")
      (node (ref "ADDER1") (pin "7") (pinfunction "C0_7") (pintype "input"))
      (node (ref "MICRO3,4") (pin "6") (pinfunction "6_6") (pintype "passive"))
    )
    (net (code "106") (name "SUM_CO") (class "Default")
      (node (ref "ADDER2") (pin "9") (pinfunction "C4_9") (pintype "output"))
      (node (ref "AND1") (pin "4") (pinfunction "I0_4") (pintype "input"))
    )
    (net (code "107") (name "VCC") (class "Default")
      (node (ref "ADDER4") (pin "16") (pinfunction "VCC_16") (pintype "power_in"))
      (node (ref "ADDER5") (pin "16") (pinfunction "VCC_16") (pintype "power_in"))
      (node (ref "AND1") (pin "14") (pinfunction "VCC_14") (pintype "power_in"))
      (node (ref "AND2") (pin "14") (pinfunction "VCC_14") (pintype "power_in"))
      (node (ref "AND3") (pin "14") (pinfunction "VCC_14") (pintype "power_in"))
      (node (ref "AND4") (pin "14") (pinfunction "VCC_14") (pintype "power_in"))
      (node (ref "AND5") (pin "14") (pinfunction "VCC_14") (pintype "power_in"))
      (node (ref "B_BUFF") (pin "1") (pinfunction "DIR_1") (pintype "input"))
      (node (ref "C1") (pin "1") (pinfunction "1_1") (pintype "passive"))
      (node (ref "MUL_BUFF") (pin "1") (pinfunction "DIR_1") (pintype "input"))
      (node (ref "NAND1") (pin "14") (pinfunction "VCC_14") (pintype "power_in"))
      (node (ref "NAND2") (pin "14") (pinfunction "VCC_14") (pintype "power_in"))
      (node (ref "NAND_BUFF") (pin "1") (pinfunction "DIR_1") (pintype "input"))
      (node (ref "NOR") (pin "14") (pinfunction "VDD_14") (pintype "power_in"))
      (node (ref "NOT") (pin "14") (pinfunction "VCC_14") (pintype "power_in"))
      (node (ref "POWER") (pin "2") (pinfunction "2_2") (pintype "passive"))
      (node (ref "SUM_BUFF") (pin "1") (pinfunction "DIR_1") (pintype "input"))
    )
    (net (code "108") (name "unconnected-(AUX-Pad1)") (class "Default")
      (node (ref "AUX") (pin "1") (pinfunction "1_1") (pintype "passive"))
    )
    (net (code "109") (name "unconnected-(AUX-Pad2)") (class "Default")
      (node (ref "AUX") (pin "2") (pinfunction "2_2") (pintype "passive"))
    )
    (net (code "110") (name "unconnected-(AUX-Pad3)") (class "Default")
      (node (ref "AUX") (pin "3") (pinfunction "3_3") (pintype "passive"))
    )
    (net (code "111") (name "unconnected-(AUX-Pad4)") (class "Default")
      (node (ref "AUX") (pin "4") (pinfunction "4_4") (pintype "passive"))
    )
    (net (code "112") (name "unconnected-(AUX-Pad5)") (class "Default")
      (node (ref "AUX") (pin "5") (pinfunction "5_5") (pintype "passive"))
    )
    (net (code "113") (name "unconnected-(AUX-Pad6)") (class "Default")
      (node (ref "AUX") (pin "6") (pinfunction "6_6") (pintype "passive"))
    )
    (net (code "114") (name "unconnected-(AUX-Pad7)") (class "Default")
      (node (ref "AUX") (pin "7") (pinfunction "7_7") (pintype "passive"))
    )
    (net (code "115") (name "unconnected-(AUX-Pad8)") (class "Default")
      (node (ref "AUX") (pin "8") (pinfunction "8_8") (pintype "passive"))
    )
    (net (code "116") (name "unconnected-(AUX1-Pad1)") (class "Default")
      (node (ref "AUX1") (pin "1") (pinfunction "1_1") (pintype "passive"))
    )
    (net (code "117") (name "unconnected-(AUX1-Pad2)") (class "Default")
      (node (ref "AUX1") (pin "2") (pinfunction "2_2") (pintype "passive"))
    )
    (net (code "118") (name "unconnected-(AUX1-Pad3)") (class "Default")
      (node (ref "AUX1") (pin "3") (pinfunction "3_3") (pintype "passive"))
    )
    (net (code "119") (name "unconnected-(AUX1-Pad4)") (class "Default")
      (node (ref "AUX1") (pin "4") (pinfunction "4_4") (pintype "passive"))
    )
    (net (code "120") (name "unconnected-(AUX1-Pad5)") (class "Default")
      (node (ref "AUX1") (pin "5") (pinfunction "5_5") (pintype "passive"))
    )
    (net (code "121") (name "unconnected-(AUX1-Pad6)") (class "Default")
      (node (ref "AUX1") (pin "6") (pinfunction "6_6") (pintype "passive"))
    )
    (net (code "122") (name "unconnected-(AUX1-Pad7)") (class "Default")
      (node (ref "AUX1") (pin "7") (pinfunction "7_7") (pintype "passive"))
    )
    (net (code "123") (name "unconnected-(AUX1-Pad8)") (class "Default")
      (node (ref "AUX1") (pin "8") (pinfunction "8_8") (pintype "passive"))
    )
    (net (code "124") (name "unconnected-(AUX2-Pad1)") (class "Default")
      (node (ref "AUX2") (pin "1") (pinfunction "1_1") (pintype "passive"))
    )
    (net (code "125") (name "unconnected-(AUX2-Pad2)") (class "Default")
      (node (ref "AUX2") (pin "2") (pinfunction "2_2") (pintype "passive"))
    )
    (net (code "126") (name "unconnected-(AUX2-Pad3)") (class "Default")
      (node (ref "AUX2") (pin "3") (pinfunction "3_3") (pintype "passive"))
    )
    (net (code "127") (name "unconnected-(AUX2-Pad4)") (class "Default")
      (node (ref "AUX2") (pin "4") (pinfunction "4_4") (pintype "passive"))
    )
    (net (code "128") (name "unconnected-(AUX2-Pad5)") (class "Default")
      (node (ref "AUX2") (pin "5") (pinfunction "5_5") (pintype "passive"))
    )
    (net (code "129") (name "unconnected-(AUX2-Pad6)") (class "Default")
      (node (ref "AUX2") (pin "6") (pinfunction "6_6") (pintype "passive"))
    )
    (net (code "130") (name "unconnected-(AUX2-Pad7)") (class "Default")
      (node (ref "AUX2") (pin "7") (pinfunction "7_7") (pintype "passive"))
    )
    (net (code "131") (name "unconnected-(AUX2-Pad8)") (class "Default")
      (node (ref "AUX2") (pin "8") (pinfunction "8_8") (pintype "passive"))
    )
    (net (code "132") (name "unconnected-(AUX3-Pad1)") (class "Default")
      (node (ref "AUX3") (pin "1") (pinfunction "1_1") (pintype "passive"))
    )
    (net (code "133") (name "unconnected-(AUX3-Pad2)") (class "Default")
      (node (ref "AUX3") (pin "2") (pinfunction "2_2") (pintype "passive"))
    )
    (net (code "134") (name "unconnected-(AUX3-Pad3)") (class "Default")
      (node (ref "AUX3") (pin "3") (pinfunction "3_3") (pintype "passive"))
    )
    (net (code "135") (name "unconnected-(AUX3-Pad4)") (class "Default")
      (node (ref "AUX3") (pin "4") (pinfunction "4_4") (pintype "passive"))
    )
    (net (code "136") (name "unconnected-(AUX3-Pad5)") (class "Default")
      (node (ref "AUX3") (pin "5") (pinfunction "5_5") (pintype "passive"))
    )
    (net (code "137") (name "unconnected-(AUX3-Pad6)") (class "Default")
      (node (ref "AUX3") (pin "6") (pinfunction "6_6") (pintype "passive"))
    )
    (net (code "138") (name "unconnected-(AUX3-Pad7)") (class "Default")
      (node (ref "AUX3") (pin "7") (pinfunction "7_7") (pintype "passive"))
    )
    (net (code "139") (name "unconnected-(AUX3-Pad8)") (class "Default")
      (node (ref "AUX3") (pin "8") (pinfunction "8_8") (pintype "passive"))
    )
    (net (code "140") (name "unconnected-(AUX4-Pad1)") (class "Default")
      (node (ref "AUX4") (pin "1") (pinfunction "1_1") (pintype "passive"))
    )
    (net (code "141") (name "unconnected-(AUX4-Pad2)") (class "Default")
      (node (ref "AUX4") (pin "2") (pinfunction "2_2") (pintype "passive"))
    )
    (net (code "142") (name "unconnected-(AUX4-Pad3)") (class "Default")
      (node (ref "AUX4") (pin "3") (pinfunction "3_3") (pintype "passive"))
    )
    (net (code "143") (name "unconnected-(AUX4-Pad4)") (class "Default")
      (node (ref "AUX4") (pin "4") (pinfunction "4_4") (pintype "passive"))
    )
    (net (code "144") (name "unconnected-(AUX4-Pad5)") (class "Default")
      (node (ref "AUX4") (pin "5") (pinfunction "5_5") (pintype "passive"))
    )
    (net (code "145") (name "unconnected-(AUX4-Pad6)") (class "Default")
      (node (ref "AUX4") (pin "6") (pinfunction "6_6") (pintype "passive"))
    )
    (net (code "146") (name "unconnected-(AUX4-Pad7)") (class "Default")
      (node (ref "AUX4") (pin "7") (pinfunction "7_7") (pintype "passive"))
    )
    (net (code "147") (name "unconnected-(AUX4-Pad8)") (class "Default")
      (node (ref "AUX4") (pin "8") (pinfunction "8_8") (pintype "passive"))
    )
    (net (code "148") (name "unconnected-(CTRL-Pad8)") (class "Default")
      (node (ref "CTRL") (pin "8") (pinfunction "8_8") (pintype "passive"))
    )
    (net (code "149") (name "unconnected-(FLAGS-Pad7)") (class "Default")
      (node (ref "FLAGS") (pin "7") (pinfunction "7_7") (pintype "passive"))
    )
    (net (code "150") (name "unconnected-(FLAGS-Pad8)") (class "Default")
      (node (ref "FLAGS") (pin "8") (pinfunction "8_8") (pintype "passive"))
    )
    (net (code "151") (name "unconnected-(FLAG_REGA-Q4-Pad6)") (class "Default")
      (node (ref "FLAG_REG") (pin "6") (pinfunction "Q4_6") (pintype "tri_state"))
    )
    (net (code "152") (name "unconnected-(MICRO1,2-Pad2)") (class "Default")
      (node (ref "MICRO1,2") (pin "2") (pinfunction "2_2") (pintype "passive"))
    )
    (net (code "153") (name "unconnected-(MICRO1,2-Pad4)") (class "Default")
      (node (ref "MICRO1,2") (pin "4") (pinfunction "4_4") (pintype "passive"))
    )
    (net (code "154") (name "unconnected-(MICRO1,2-Pad6)") (class "Default")
      (node (ref "MICRO1,2") (pin "6") (pinfunction "6_6") (pintype "passive"))
    )
    (net (code "155") (name "unconnected-(MICRO1,2-Pad8)") (class "Default")
      (node (ref "MICRO1,2") (pin "8") (pinfunction "8_8") (pintype "passive"))
    )
    (net (code "156") (name "unconnected-(MICRO1,2-Pad10)") (class "Default")
      (node (ref "MICRO1,2") (pin "10") (pinfunction "10_10") (pintype "passive"))
    )
    (net (code "157") (name "unconnected-(MICRO1,2-Pad16)") (class "Default")
      (node (ref "MICRO1,2") (pin "16") (pinfunction "16_16") (pintype "passive"))
    )
    (net (code "158") (name "unconnected-(MICRO3,4-Pad10)") (class "Default")
      (node (ref "MICRO3,4") (pin "10") (pinfunction "10_10") (pintype "passive"))
    )
    (net (code "159") (name "unconnected-(MICRO5,6-Pad1)") (class "Default")
      (node (ref "MICRO5,6") (pin "1") (pinfunction "1_1") (pintype "passive"))
    )
    (net (code "160") (name "unconnected-(MICRO5,6-Pad2)") (class "Default")
      (node (ref "MICRO5,6") (pin "2") (pinfunction "2_2") (pintype "passive"))
    )
    (net (code "161") (name "unconnected-(MICRO5,6-Pad3)") (class "Default")
      (node (ref "MICRO5,6") (pin "3") (pinfunction "3_3") (pintype "passive"))
    )
    (net (code "162") (name "unconnected-(MICRO5,6-Pad4)") (class "Default")
      (node (ref "MICRO5,6") (pin "4") (pinfunction "4_4") (pintype "passive"))
    )
    (net (code "163") (name "unconnected-(MICRO5,6-Pad5)") (class "Default")
      (node (ref "MICRO5,6") (pin "5") (pinfunction "5_5") (pintype "passive"))
    )
    (net (code "164") (name "unconnected-(MICRO5,6-Pad6)") (class "Default")
      (node (ref "MICRO5,6") (pin "6") (pinfunction "6_6") (pintype "passive"))
    )
    (net (code "165") (name "unconnected-(MICRO5,6-Pad7)") (class "Default")
      (node (ref "MICRO5,6") (pin "7") (pinfunction "7_7") (pintype "passive"))
    )
    (net (code "166") (name "unconnected-(MICRO5,6-Pad8)") (class "Default")
      (node (ref "MICRO5,6") (pin "8") (pinfunction "8_8") (pintype "passive"))
    )
    (net (code "167") (name "unconnected-(MICRO5,6-Pad9)") (class "Default")
      (node (ref "MICRO5,6") (pin "9") (pinfunction "9_9") (pintype "passive"))
    )
    (net (code "168") (name "unconnected-(MICRO5,6-Pad10)") (class "Default")
      (node (ref "MICRO5,6") (pin "10") (pinfunction "10_10") (pintype "passive"))
    )
    (net (code "169") (name "unconnected-(MICRO5,6-Pad11)") (class "Default")
      (node (ref "MICRO5,6") (pin "11") (pinfunction "11_11") (pintype "passive"))
    )
    (net (code "170") (name "unconnected-(MICRO5,6-Pad12)") (class "Default")
      (node (ref "MICRO5,6") (pin "12") (pinfunction "12_12") (pintype "passive"))
    )
    (net (code "171") (name "unconnected-(MICRO5,6-Pad13)") (class "Default")
      (node (ref "MICRO5,6") (pin "13") (pinfunction "13_13") (pintype "passive"))
    )
    (net (code "172") (name "unconnected-(MICRO5,6-Pad14)") (class "Default")
      (node (ref "MICRO5,6") (pin "14") (pinfunction "14_14") (pintype "passive"))
    )
    (net (code "173") (name "unconnected-(MICRO5,6-Pad15)") (class "Default")
      (node (ref "MICRO5,6") (pin "15") (pinfunction "15_15") (pintype "passive"))
    )
    (net (code "174") (name "unconnected-(MICRO5,6-Pad16)") (class "Default")
      (node (ref "MICRO5,6") (pin "16") (pinfunction "16_16") (pintype "passive"))
    )
    (net (code "175") (name "~{CLK}") (class "Default")
      (node (ref "CTRL") (pin "2") (pinfunction "2_2") (pintype "passive"))
    )
    (net (code "176") (name "~{FL_C}") (class "Default")
      (node (ref "FLAGS") (pin "6") (pinfunction "6_6") (pintype "passive"))
      (node (ref "NOT") (pin "6") (pinfunction "O_6") (pintype "output"))
    )
    (net (code "177") (name "~{FL_N}") (class "Default")
      (node (ref "FLAGS") (pin "4") (pinfunction "4_4") (pintype "passive"))
      (node (ref "NOT") (pin "4") (pinfunction "O_4") (pintype "output"))
    )
    (net (code "178") (name "~{FL_Z}") (class "Default")
      (node (ref "FLAGS") (pin "2") (pinfunction "2_2") (pintype "passive"))
      (node (ref "NOT") (pin "2") (pinfunction "O_2") (pintype "output"))
    )
    (net (code "179") (name "~{HALT}") (class "Default")
      (node (ref "MICRO1,2") (pin "15") (pinfunction "15_15") (pintype "passive"))
    )
    (net (code "180") (name "~{PROG}") (class "Default")
      (node (ref "CTRL") (pin "6") (pinfunction "6_6") (pintype "passive"))
    )
    (net (code "181") (name "~{RD_ALU}") (class "Default")
      (node (ref "MICRO3,4") (pin "2") (pinfunction "2_2") (pintype "passive"))
    )
    (net (code "182") (name "~{RD_B}") (class "Default")
      (node (ref "B_BUFF") (pin "19") (pinfunction "G_19") (pintype "input"))
      (node (ref "OP_SEL") (pin "4") (pinfunction "Y0_4") (pintype "output"))
    )
    (net (code "183") (name "~{RD_MUL}") (class "Default")
      (node (ref "MUL_BUFF") (pin "19") (pinfunction "G_19") (pintype "input"))
      (node (ref "OP_SEL") (pin "6") (pinfunction "Y2_6") (pintype "output"))
    )
    (net (code "184") (name "~{RD_NAND}") (class "Default")
      (node (ref "NAND_BUFF") (pin "19") (pinfunction "G_19") (pintype "input"))
      (node (ref "OP_SEL") (pin "7") (pinfunction "Y3_7") (pintype "output"))
    )
    (net (code "185") (name "~{RD_PC}") (class "Default")
      (node (ref "MICRO1,2") (pin "3") (pinfunction "3_3") (pintype "passive"))
    )
    (net (code "186") (name "~{RD_ROM}") (class "Default")
      (node (ref "MICRO1,2") (pin "9") (pinfunction "9_9") (pintype "passive"))
    )
    (net (code "187") (name "~{RD_SUM}") (class "Default")
      (node (ref "NOT") (pin "9") (pinfunction "I_9") (pintype "input"))
      (node (ref "OP_SEL") (pin "5") (pinfunction "Y1_5") (pintype "output"))
      (node (ref "SUM_BUFF") (pin "19") (pinfunction "G_19") (pintype "input"))
    )
    (net (code "188") (name "~{RST}") (class "Default")
      (node (ref "CTRL") (pin "4") (pinfunction "4_4") (pintype "passive"))
    )
    (net (code "189") (name "~{WR_A}") (class "Default")
      (node (ref "MICRO3,4") (pin "1") (pinfunction "1_1") (pintype "passive"))
    )
    (net (code "190") (name "~{WR_B}") (class "Default")
      (node (ref "MICRO3,4") (pin "3") (pinfunction "3_3") (pintype "passive"))
    )
    (net (code "191") (name "~{WR_FL}") (class "Default")
      (node (ref "FLAG_REG") (pin "10") (pinfunction "G2_10") (pintype "input"))
      (node (ref "FLAG_REG") (pin "9") (pinfunction "G1_9") (pintype "input"))
      (node (ref "MICRO3,4") (pin "4") (pinfunction "4_4") (pintype "passive"))
    )
    (net (code "192") (name "~{WR_IR}") (class "Default")
      (node (ref "MICRO1,2") (pin "11") (pinfunction "11_11") (pintype "passive"))
    )
    (net (code "193") (name "~{WR_MAR}") (class "Default")
      (node (ref "MICRO1,2") (pin "5") (pinfunction "5_5") (pintype "passive"))
    )
    (net (code "194") (name "~{WR_OUT}") (class "Default")
      (node (ref "MICRO1,2") (pin "13") (pinfunction "13_13") (pintype "passive"))
    )
    (net (code "195") (name "~{WR_ROM}") (class "Default")
      (node (ref "MICRO1,2") (pin "7") (pinfunction "7_7") (pintype "passive"))
    )
    (net (code "196") (name "~{WR_STACK}") (class "Default")
      (node (ref "MICRO3,4") (pin "7") (pinfunction "7_7") (pintype "passive"))
    )
    (net (code "197") (name "~{WR_Y}") (class "Default")
      (node (ref "MICRO3,4") (pin "5") (pinfunction "5_5") (pintype "passive"))
    )
  )
)
